# F-rev04.net
KiCad netlist of a schematic drawn in EAGLE
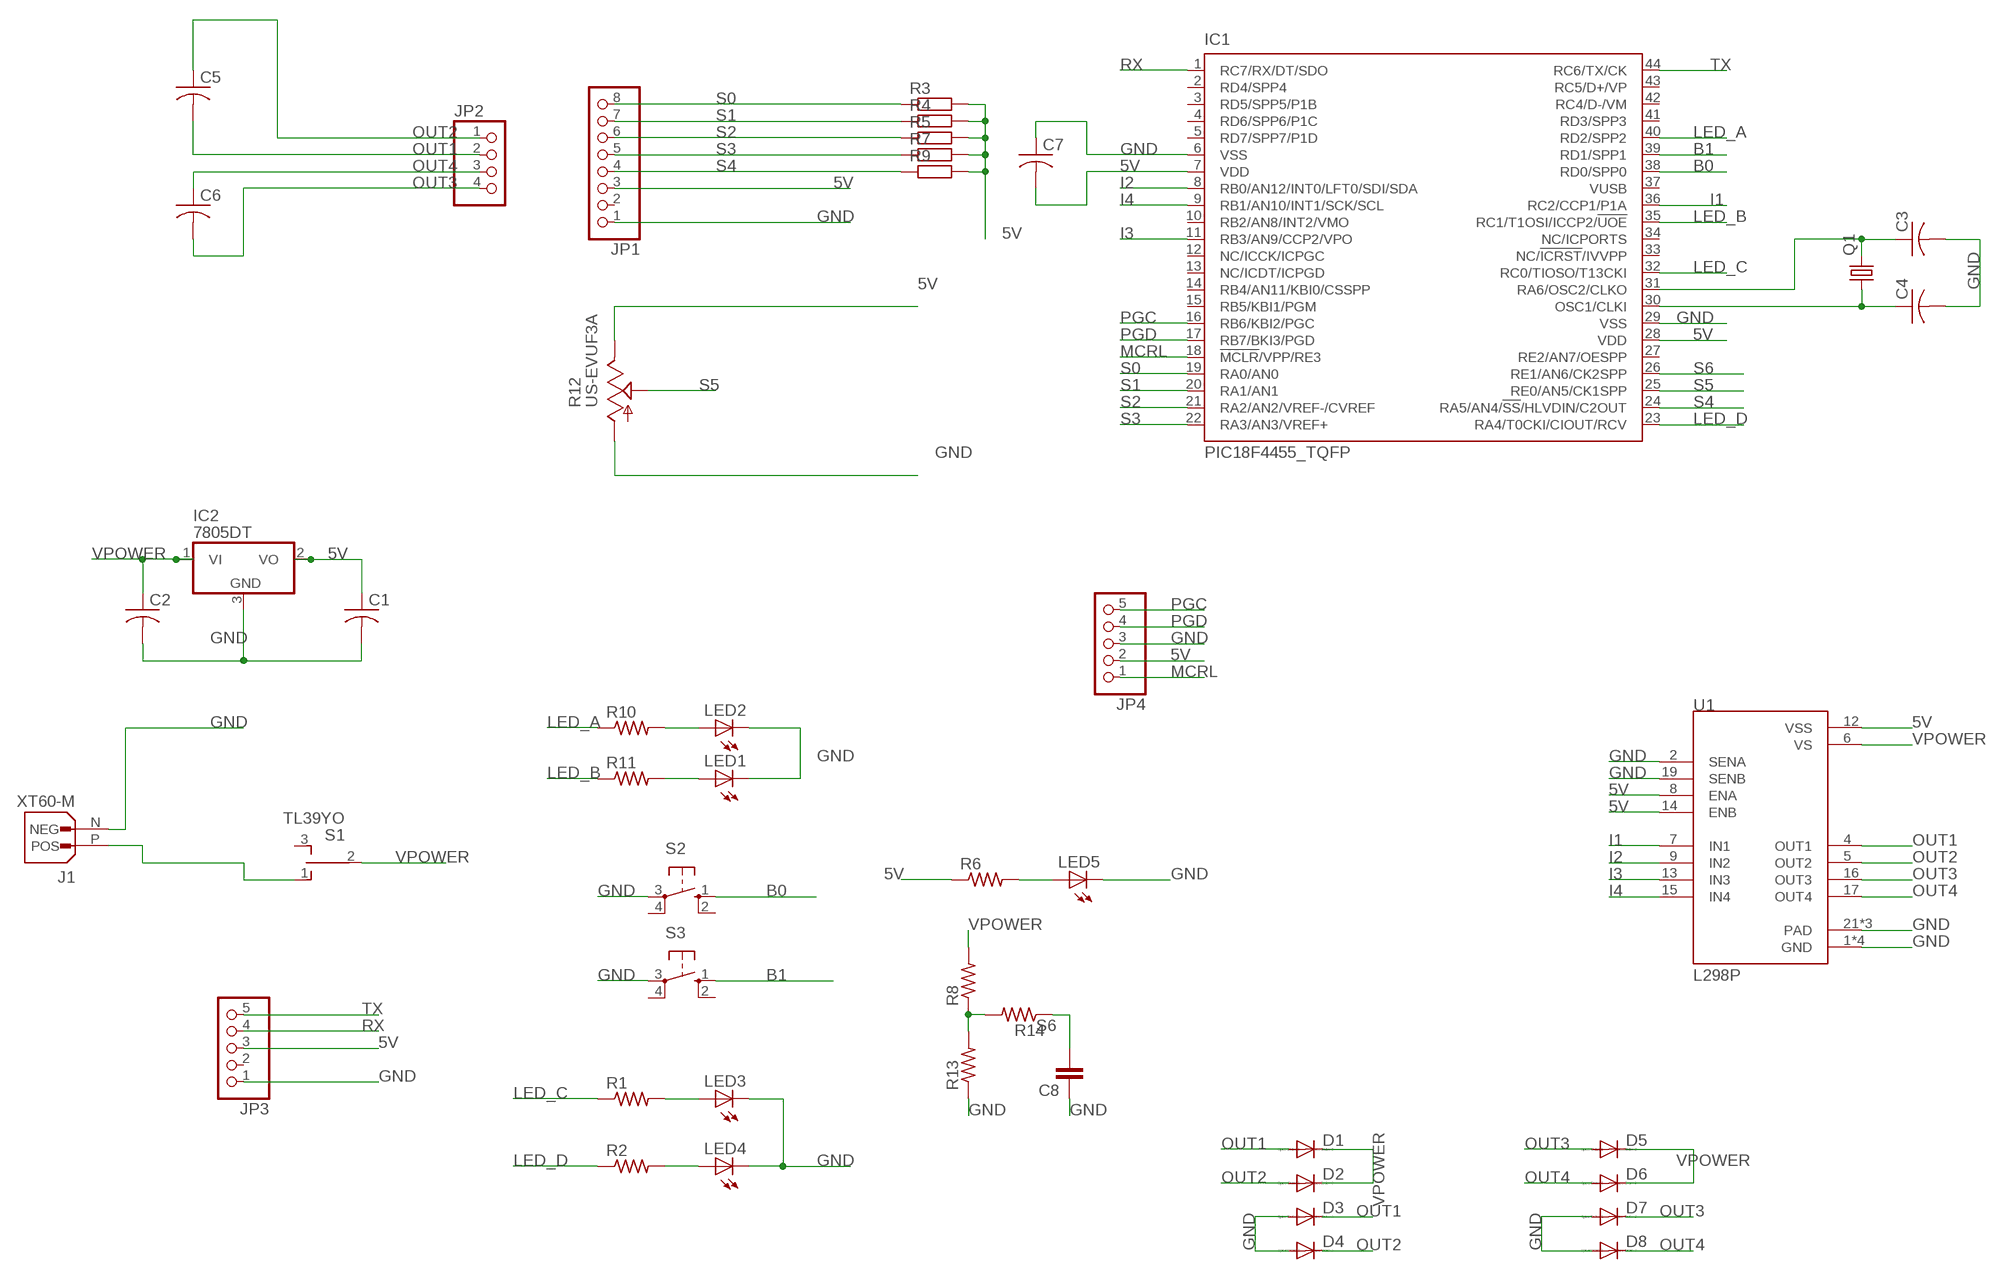
[diagram p0: schematic, sheet 1]

(export (version "E")
  (design (tool "Eeschema 10.0.6"))
  (components
    (comp (ref "C1")
      (value "C-USC0805K")
      (footprint "eagle-import:C0805K")
      (libsource (lib "eagle-import") (part "C-USC0805K"))
    )
    (comp (ref "C2")
      (value "C-USC0805K")
      (footprint "eagle-import:C0805K")
      (libsource (lib "eagle-import") (part "C-USC0805K"))
    )
    (comp (ref "C3")
      (value "C-USC0805K")
      (footprint "eagle-import:C0805K")
      (libsource (lib "eagle-import") (part "C-USC0805K"))
    )
    (comp (ref "C4")
      (value "C-USC0805K")
      (footprint "eagle-import:C0805K")
      (libsource (lib "eagle-import") (part "C-USC0805K"))
    )
    (comp (ref "C5")
      (value "C-USC0805K")
      (footprint "eagle-import:C0805K")
      (libsource (lib "eagle-import") (part "C-USC0805K"))
    )
    (comp (ref "C6")
      (value "C-USC0805K")
      (footprint "eagle-import:C0805K")
      (libsource (lib "eagle-import") (part "C-USC0805K"))
    )
    (comp (ref "C7")
      (value "C-USC0805K")
      (footprint "eagle-import:C0805K")
      (libsource (lib "eagle-import") (part "C-USC0805K"))
    )
    (comp (ref "C8")
      (value "C2,5-3")
      (footprint "eagle-import:C2.5-3")
      (libsource (lib "eagle-import") (part "C2,5-3"))
    )
    (comp (ref "D1")
      (value "DIODE-DO214AC")
      (footprint "eagle-import:DO214AC")
      (libsource (lib "eagle-import") (part "DIODE-DO214AC"))
    )
    (comp (ref "D2")
      (value "DIODE-DO214AC")
      (footprint "eagle-import:DO214AC")
      (libsource (lib "eagle-import") (part "DIODE-DO214AC"))
    )
    (comp (ref "D3")
      (value "DIODE-DO214AC")
      (footprint "eagle-import:DO214AC")
      (libsource (lib "eagle-import") (part "DIODE-DO214AC"))
    )
    (comp (ref "D4")
      (value "DIODE-DO214AC")
      (footprint "eagle-import:DO214AC")
      (libsource (lib "eagle-import") (part "DIODE-DO214AC"))
    )
    (comp (ref "D5")
      (value "DIODE-DO214AC")
      (footprint "eagle-import:DO214AC")
      (libsource (lib "eagle-import") (part "DIODE-DO214AC"))
    )
    (comp (ref "D6")
      (value "DIODE-DO214AC")
      (footprint "eagle-import:DO214AC")
      (libsource (lib "eagle-import") (part "DIODE-DO214AC"))
    )
    (comp (ref "D7")
      (value "DIODE-DO214AC")
      (footprint "eagle-import:DO214AC")
      (libsource (lib "eagle-import") (part "DIODE-DO214AC"))
    )
    (comp (ref "D8")
      (value "DIODE-DO214AC")
      (footprint "eagle-import:DO214AC")
      (libsource (lib "eagle-import") (part "DIODE-DO214AC"))
    )
    (comp (ref "IC1")
      (value "PIC18F4455_TQFP")
      (footprint "eagle-import:TQFP44")
      (fields (field (name "MF") "MICROCHIP") (field (name "MPN") "PIC18F4455-I/PT"))
      (libsource (lib "eagle-import") (part "PIC18F4_TQFP455"))
    )
    (comp (ref "IC2")
      (value "7805DT")
      (footprint "eagle-import:TO252")
      (libsource (lib "eagle-import") (part "78DT05"))
    )
    (comp (ref "J1")
      (value "XT60-M")
      (footprint "eagle-import:AMASS_XT60-M")
      (fields (field (name "MF") "AMASS"))
      (libsource (lib "eagle-import") (part "XT60-M"))
    )
    (comp (ref "JP1")
      (value "PINHD-1X8")
      (footprint "eagle-import:1X08")
      (libsource (lib "eagle-import") (part "PINHD-1X8"))
    )
    (comp (ref "JP2")
      (value "PINHD-1X4")
      (footprint "eagle-import:1X04")
      (libsource (lib "eagle-import") (part "PINHD-1X4"))
    )
    (comp (ref "JP3")
      (value "PINHD-1X5")
      (footprint "eagle-import:1X05")
      (libsource (lib "eagle-import") (part "PINHD-1X5"))
    )
    (comp (ref "JP4")
      (value "PINHD-1X5")
      (footprint "eagle-import:1X05")
      (libsource (lib "eagle-import") (part "PINHD-1X5"))
    )
    (comp (ref "LED1")
      (value "LEDCHIPLED_1206")
      (footprint "eagle-import:CHIPLED_1206")
      (libsource (lib "eagle-import") (part "LEDCHIPLED_1206"))
    )
    (comp (ref "LED2")
      (value "LEDCHIPLED_1206")
      (footprint "eagle-import:CHIPLED_1206")
      (libsource (lib "eagle-import") (part "LEDCHIPLED_1206"))
    )
    (comp (ref "LED3")
      (value "LEDCHIPLED_1206")
      (footprint "eagle-import:CHIPLED_1206")
      (libsource (lib "eagle-import") (part "LEDCHIPLED_1206"))
    )
    (comp (ref "LED4")
      (value "LEDCHIPLED_1206")
      (footprint "eagle-import:CHIPLED_1206")
      (libsource (lib "eagle-import") (part "LEDCHIPLED_1206"))
    )
    (comp (ref "LED5")
      (value "LEDCHIPLED_1206")
      (footprint "eagle-import:CHIPLED_1206")
      (libsource (lib "eagle-import") (part "LEDCHIPLED_1206"))
    )
    (comp (ref "Q1")
      (value "CRYSTALHC49S")
      (footprint "eagle-import:HC49_S")
      (libsource (lib "eagle-import") (part "CRYSTALHC49S"))
    )
    (comp (ref "R1")
      (value "R-US_R0805")
      (footprint "eagle-import:R0805")
      (libsource (lib "eagle-import") (part "resistor_R-US_R0805"))
    )
    (comp (ref "R2")
      (value "R-US_R0805")
      (footprint "eagle-import:R0805")
      (libsource (lib "eagle-import") (part "resistor_R-US_R0805"))
    )
    (comp (ref "R3")
      (value "R-EU_M0805")
      (footprint "eagle-import:M0805")
      (libsource (lib "eagle-import") (part "R-EU_M0805"))
    )
    (comp (ref "R4")
      (value "R-EU_M0805")
      (footprint "eagle-import:M0805")
      (libsource (lib "eagle-import") (part "R-EU_M0805"))
    )
    (comp (ref "R5")
      (value "R-EU_M0805")
      (footprint "eagle-import:M0805")
      (libsource (lib "eagle-import") (part "R-EU_M0805"))
    )
    (comp (ref "R6")
      (value "R-US_M0805")
      (footprint "eagle-import:M0805")
      (libsource (lib "eagle-import") (part "R-US_M0805"))
    )
    (comp (ref "R7")
      (value "R-EU_M0805")
      (footprint "eagle-import:M0805")
      (libsource (lib "eagle-import") (part "R-EU_M0805"))
    )
    (comp (ref "R8")
      (value "R-US_M0805")
      (footprint "eagle-import:M0805")
      (libsource (lib "eagle-import") (part "R-US_M0805"))
    )
    (comp (ref "R9")
      (value "R-EU_M0805")
      (footprint "eagle-import:M0805")
      (libsource (lib "eagle-import") (part "R-EU_M0805"))
    )
    (comp (ref "R10")
      (value "R-US_M0805")
      (footprint "eagle-import:M0805")
      (libsource (lib "eagle-import") (part "R-US_M0805"))
    )
    (comp (ref "R11")
      (value "R-US_M0805")
      (footprint "eagle-import:M0805")
      (libsource (lib "eagle-import") (part "R-US_M0805"))
    )
    (comp (ref "R12")
      (value "US-EVUF3A")
      (footprint "eagle-import:EVUF")
      (libsource (lib "eagle-import") (part "US-EVUAF3"))
    )
    (comp (ref "R13")
      (value "R-US_M0805")
      (footprint "eagle-import:M0805")
      (libsource (lib "eagle-import") (part "R-US_M0805"))
    )
    (comp (ref "R14")
      (value "R-US_M0805")
      (footprint "eagle-import:M0805")
      (libsource (lib "eagle-import") (part "R-US_M0805"))
    )
    (comp (ref "S1")
      (value "TL39YO")
      (footprint "eagle-import:TL3XYO")
      (libsource (lib "eagle-import") (part "TL39YO"))
    )
    (comp (ref "S2")
      (value "10-XX")
      (footprint "eagle-import:B3F-10XX")
      (fields (field (name "MPN") "B3F-1000"))
      (libsource (lib "eagle-import") (part "10-XX"))
    )
    (comp (ref "S3")
      (value "10-XX")
      (footprint "eagle-import:B3F-10XX")
      (fields (field (name "MPN") "B3F-1000"))
      (libsource (lib "eagle-import") (part "10-XX"))
    )
    (comp (ref "U1")
      (value "L298P")
      (footprint "eagle-import:SOIC127P1420X360-20N")
      (fields (field (name "MF") "STMicroelectronics"))
      (libsource (lib "eagle-import") (part "L298P"))
    )
  )
  (nets
    (net (code "1") (name "/5V") (class "Default")
      (node (ref "C1") (pin "1") (pinfunction "1_1") (pintype "passive"))
      (node (ref "C7") (pin "2") (pinfunction "2_2") (pintype "passive"))
      (node (ref "IC1") (pin "28") (pinfunction "VDD_28") (pintype "power_in"))
      (node (ref "IC1") (pin "7") (pinfunction "VDD_7") (pintype "power_in"))
      (node (ref "IC2") (pin "2") (pinfunction "VO_2") (pintype "passive"))
      (node (ref "JP1") (pin "3") (pinfunction "3_3") (pintype "passive"))
      (node (ref "JP3") (pin "3") (pinfunction "3_3") (pintype "passive"))
      (node (ref "JP4") (pin "2") (pinfunction "2_2") (pintype "passive"))
      (node (ref "R12") (pin "3") (pinfunction "E_3") (pintype "passive"))
      (node (ref "R3") (pin "2") (pinfunction "2_2") (pintype "passive"))
      (node (ref "R4") (pin "2") (pinfunction "2_2") (pintype "passive"))
      (node (ref "R5") (pin "2") (pinfunction "2_2") (pintype "passive"))
      (node (ref "R6") (pin "1") (pinfunction "1_1") (pintype "passive"))
      (node (ref "R7") (pin "2") (pinfunction "2_2") (pintype "passive"))
      (node (ref "R9") (pin "2") (pinfunction "2_2") (pintype "passive"))
      (node (ref "U1") (pin "12") (pinfunction "VSS_12") (pintype "power_in"))
      (node (ref "U1") (pin "14") (pinfunction "ENB_14") (pintype "input"))
      (node (ref "U1") (pin "8") (pinfunction "ENA_8") (pintype "input"))
    )
    (net (code "2") (name "/B0") (class "Default")
      (node (ref "IC1") (pin "38") (pinfunction "RD0/SPP0_38") (pintype "bidirectional"))
      (node (ref "S2") (pin "1") (pinfunction "S_1") (pintype "passive"))
    )
    (net (code "3") (name "/B1") (class "Default")
      (node (ref "IC1") (pin "39") (pinfunction "RD1/SPP1_39") (pintype "bidirectional"))
      (node (ref "S3") (pin "1") (pinfunction "S_1") (pintype "passive"))
    )
    (net (code "4") (name "/GND") (class "Default")
      (node (ref "C1") (pin "2") (pinfunction "2_2") (pintype "passive"))
      (node (ref "C2") (pin "2") (pinfunction "2_2") (pintype "passive"))
      (node (ref "C3") (pin "2") (pinfunction "2_2") (pintype "passive"))
      (node (ref "C4") (pin "2") (pinfunction "2_2") (pintype "passive"))
      (node (ref "C7") (pin "1") (pinfunction "1_1") (pintype "passive"))
      (node (ref "C8") (pin "1") (pinfunction "1_1") (pintype "passive"))
      (node (ref "D3") (pin "A") (pinfunction "A_A") (pintype "passive"))
      (node (ref "D4") (pin "A") (pinfunction "A_A") (pintype "passive"))
      (node (ref "D7") (pin "A") (pinfunction "A_A") (pintype "passive"))
      (node (ref "D8") (pin "A") (pinfunction "A_A") (pintype "passive"))
      (node (ref "IC1") (pin "29") (pinfunction "VSS_29") (pintype "power_in"))
      (node (ref "IC1") (pin "6") (pinfunction "VSS_6") (pintype "power_in"))
      (node (ref "IC2") (pin "3") (pinfunction "GND_3") (pintype "passive"))
      (node (ref "J1") (pin "N") (pinfunction "NEG_N") (pintype "passive"))
      (node (ref "JP1") (pin "1") (pinfunction "1_1") (pintype "passive"))
      (node (ref "JP3") (pin "1") (pinfunction "1_1") (pintype "passive"))
      (node (ref "JP4") (pin "3") (pinfunction "3_3") (pintype "passive"))
      (node (ref "LED1") (pin "C") (pinfunction "C_C") (pintype "passive"))
      (node (ref "LED2") (pin "C") (pinfunction "C_C") (pintype "passive"))
      (node (ref "LED3") (pin "C") (pinfunction "C_C") (pintype "passive"))
      (node (ref "LED4") (pin "C") (pinfunction "C_C") (pintype "passive"))
      (node (ref "LED5") (pin "C") (pinfunction "C_C") (pintype "passive"))
      (node (ref "R12") (pin "1") (pinfunction "A_1") (pintype "passive"))
      (node (ref "R13") (pin "1") (pinfunction "1_1") (pintype "passive"))
      (node (ref "S2") (pin "3") (pinfunction "P_3") (pintype "passive"))
      (node (ref "S3") (pin "3") (pinfunction "P_3") (pintype "passive"))
      (node (ref "U1") (pin "1") (pinfunction "GND_1") (pintype "passive"))
      (node (ref "U1") (pin "10") (pinfunction "GND_10") (pintype "passive"))
      (node (ref "U1") (pin "11") (pinfunction "GND_11") (pintype "passive"))
      (node (ref "U1") (pin "19") (pinfunction "SENB_19") (pintype "input"))
      (node (ref "U1") (pin "2") (pinfunction "SENA_2") (pintype "input"))
      (node (ref "U1") (pin "20") (pinfunction "GND_20") (pintype "passive"))
      (node (ref "U1") (pin "21") (pinfunction "PAD_21") (pintype "passive"))
      (node (ref "U1") (pin "22") (pinfunction "PAD_22") (pintype "passive"))
      (node (ref "U1") (pin "23") (pinfunction "PAD_23") (pintype "passive"))
    )
    (net (code "5") (name "/I1") (class "Default")
      (node (ref "IC1") (pin "36") (pinfunction "RC2/CCP1/P1A_36") (pintype "bidirectional"))
      (node (ref "U1") (pin "7") (pinfunction "IN1_7") (pintype "input"))
    )
    (net (code "6") (name "/I2") (class "Default")
      (node (ref "IC1") (pin "8") (pinfunction "RB0/AN12/INT0/LFT0/SDI/SDA_8") (pintype "bidirectional"))
      (node (ref "U1") (pin "9") (pinfunction "IN2_9") (pintype "input"))
    )
    (net (code "7") (name "/I3") (class "Default")
      (node (ref "IC1") (pin "11") (pinfunction "RB3/AN9/CCP2/VPO_11") (pintype "bidirectional"))
      (node (ref "U1") (pin "13") (pinfunction "IN3_13") (pintype "input"))
    )
    (net (code "8") (name "/I4") (class "Default")
      (node (ref "IC1") (pin "9") (pinfunction "RB1/AN10/INT1/SCK/SCL_9") (pintype "bidirectional"))
      (node (ref "U1") (pin "15") (pinfunction "IN4_15") (pintype "input"))
    )
    (net (code "9") (name "/LED_A") (class "Default")
      (node (ref "IC1") (pin "40") (pinfunction "RD2/SPP2_40") (pintype "bidirectional"))
      (node (ref "R10") (pin "1") (pinfunction "1_1") (pintype "passive"))
    )
    (net (code "10") (name "/LED_B") (class "Default")
      (node (ref "IC1") (pin "35") (pinfunction "RC1/T1OSI/ICCP2/~{UOE}_35") (pintype "bidirectional"))
      (node (ref "R11") (pin "1") (pinfunction "1_1") (pintype "passive"))
    )
    (net (code "11") (name "/LED_C") (class "Default")
      (node (ref "IC1") (pin "32") (pinfunction "RC0/TIOSO/T13CKI_32") (pintype "bidirectional"))
      (node (ref "R1") (pin "1") (pinfunction "1_1") (pintype "passive"))
    )
    (net (code "12") (name "/LED_D") (class "Default")
      (node (ref "IC1") (pin "23") (pinfunction "RA4/T0CKI/CIOUT/RCV_23") (pintype "bidirectional"))
      (node (ref "R2") (pin "1") (pinfunction "1_1") (pintype "passive"))
    )
    (net (code "13") (name "/MCRL") (class "Default")
      (node (ref "IC1") (pin "18") (pinfunction "~{MCLR}/VPP/RE3_18") (pintype "input"))
      (node (ref "JP4") (pin "1") (pinfunction "1_1") (pintype "passive"))
    )
    (net (code "14") (name "/OUT1") (class "Default")
      (node (ref "C5") (pin "2") (pinfunction "2_2") (pintype "passive"))
      (node (ref "D1") (pin "A") (pinfunction "A_A") (pintype "passive"))
      (node (ref "D3") (pin "C") (pinfunction "C_C") (pintype "passive"))
      (node (ref "JP2") (pin "2") (pinfunction "2_2") (pintype "passive"))
      (node (ref "U1") (pin "4") (pinfunction "OUT1_4") (pintype "output"))
    )
    (net (code "15") (name "/OUT2") (class "Default")
      (node (ref "C5") (pin "1") (pinfunction "1_1") (pintype "passive"))
      (node (ref "D2") (pin "A") (pinfunction "A_A") (pintype "passive"))
      (node (ref "D4") (pin "C") (pinfunction "C_C") (pintype "passive"))
      (node (ref "JP2") (pin "1") (pinfunction "1_1") (pintype "passive"))
      (node (ref "U1") (pin "5") (pinfunction "OUT2_5") (pintype "output"))
    )
    (net (code "16") (name "/OUT3") (class "Default")
      (node (ref "C6") (pin "2") (pinfunction "2_2") (pintype "passive"))
      (node (ref "D5") (pin "A") (pinfunction "A_A") (pintype "passive"))
      (node (ref "D7") (pin "C") (pinfunction "C_C") (pintype "passive"))
      (node (ref "JP2") (pin "4") (pinfunction "4_4") (pintype "passive"))
      (node (ref "U1") (pin "16") (pinfunction "OUT3_16") (pintype "output"))
    )
    (net (code "17") (name "/OUT4") (class "Default")
      (node (ref "C6") (pin "1") (pinfunction "1_1") (pintype "passive"))
      (node (ref "D6") (pin "A") (pinfunction "A_A") (pintype "passive"))
      (node (ref "D8") (pin "C") (pinfunction "C_C") (pintype "passive"))
      (node (ref "JP2") (pin "3") (pinfunction "3_3") (pintype "passive"))
      (node (ref "U1") (pin "17") (pinfunction "OUT4_17") (pintype "output"))
    )
    (net (code "18") (name "/PGC") (class "Default")
      (node (ref "IC1") (pin "16") (pinfunction "RB6/KBI2/PGC_16") (pintype "bidirectional"))
      (node (ref "JP4") (pin "5") (pinfunction "5_5") (pintype "passive"))
    )
    (net (code "19") (name "/PGD") (class "Default")
      (node (ref "IC1") (pin "17") (pinfunction "RB7/BKI3/PGD_17") (pintype "bidirectional"))
      (node (ref "JP4") (pin "4") (pinfunction "4_4") (pintype "passive"))
    )
    (net (code "20") (name "/RX") (class "Default")
      (node (ref "IC1") (pin "1") (pinfunction "RC7/RX/DT/SDO_1") (pintype "bidirectional"))
      (node (ref "JP3") (pin "4") (pinfunction "4_4") (pintype "passive"))
    )
    (net (code "21") (name "/S0") (class "Default")
      (node (ref "IC1") (pin "19") (pinfunction "RA0/AN0_19") (pintype "bidirectional"))
      (node (ref "JP1") (pin "8") (pinfunction "8_8") (pintype "passive"))
      (node (ref "R3") (pin "1") (pinfunction "1_1") (pintype "passive"))
    )
    (net (code "22") (name "/S1") (class "Default")
      (node (ref "IC1") (pin "20") (pinfunction "RA1/AN1_20") (pintype "bidirectional"))
      (node (ref "JP1") (pin "7") (pinfunction "7_7") (pintype "passive"))
      (node (ref "R4") (pin "1") (pinfunction "1_1") (pintype "passive"))
    )
    (net (code "23") (name "/S2") (class "Default")
      (node (ref "IC1") (pin "21") (pinfunction "RA2/AN2/VREF-/CVREF_21") (pintype "bidirectional"))
      (node (ref "JP1") (pin "6") (pinfunction "6_6") (pintype "passive"))
      (node (ref "R5") (pin "1") (pinfunction "1_1") (pintype "passive"))
    )
    (net (code "24") (name "/S3") (class "Default")
      (node (ref "IC1") (pin "22") (pinfunction "RA3/AN3/VREF+_22") (pintype "bidirectional"))
      (node (ref "JP1") (pin "5") (pinfunction "5_5") (pintype "passive"))
      (node (ref "R7") (pin "1") (pinfunction "1_1") (pintype "passive"))
    )
    (net (code "25") (name "/S4") (class "Default")
      (node (ref "IC1") (pin "24") (pinfunction "RA5/AN4/~{SS}/HLVDIN/C2OUT_24") (pintype "bidirectional"))
      (node (ref "JP1") (pin "4") (pinfunction "4_4") (pintype "passive"))
      (node (ref "R9") (pin "1") (pinfunction "1_1") (pintype "passive"))
    )
    (net (code "26") (name "/S5") (class "Default")
      (node (ref "IC1") (pin "25") (pinfunction "RE0/AN5/CK1SPP_25") (pintype "bidirectional"))
      (node (ref "R12") (pin "2") (pinfunction "S_2") (pintype "passive"))
    )
    (net (code "27") (name "/S6") (class "Default")
      (node (ref "C8") (pin "2") (pinfunction "2_2") (pintype "passive"))
      (node (ref "IC1") (pin "26") (pinfunction "RE1/AN6/CK2SPP_26") (pintype "bidirectional"))
      (node (ref "R14") (pin "1") (pinfunction "1_1") (pintype "passive"))
    )
    (net (code "28") (name "/TX") (class "Default")
      (node (ref "IC1") (pin "44") (pinfunction "RC6/TX/CK_44") (pintype "bidirectional"))
      (node (ref "JP3") (pin "5") (pinfunction "5_5") (pintype "passive"))
    )
    (net (code "29") (name "/VPOWER") (class "Default")
      (node (ref "C2") (pin "1") (pinfunction "1_1") (pintype "passive"))
      (node (ref "D1") (pin "C") (pinfunction "C_C") (pintype "passive"))
      (node (ref "D2") (pin "C") (pinfunction "C_C") (pintype "passive"))
      (node (ref "D5") (pin "C") (pinfunction "C_C") (pintype "passive"))
      (node (ref "D6") (pin "C") (pinfunction "C_C") (pintype "passive"))
      (node (ref "IC2") (pin "1") (pinfunction "VI_1") (pintype "input"))
      (node (ref "R8") (pin "2") (pinfunction "2_2") (pintype "passive"))
      (node (ref "S1") (pin "2") (pinfunction "P_2") (pintype "passive"))
      (node (ref "U1") (pin "6") (pinfunction "VS_6") (pintype "power_in"))
    )
    (net (code "30") (name "Net-(IC1-OSC1{slash}CLKI)") (class "Default")
      (node (ref "C4") (pin "1") (pinfunction "1_1") (pintype "passive"))
      (node (ref "IC1") (pin "30") (pinfunction "OSC1/CLKI_30") (pintype "input"))
      (node (ref "Q1") (pin "1") (pinfunction "1_1") (pintype "passive"))
    )
    (net (code "31") (name "Net-(IC1-RA6{slash}OSC2{slash}CLKO)") (class "Default")
      (node (ref "C3") (pin "1") (pinfunction "1_1") (pintype "passive"))
      (node (ref "IC1") (pin "31") (pinfunction "RA6/OSC2/CLKO_31") (pintype "output"))
      (node (ref "Q1") (pin "2") (pinfunction "2_2") (pintype "passive"))
    )
    (net (code "32") (name "Net-(J1-POS)") (class "Default")
      (node (ref "J1") (pin "P") (pinfunction "POS_P") (pintype "passive"))
      (node (ref "S1") (pin "1") (pinfunction "O_1") (pintype "passive"))
    )
    (net (code "33") (name "Net-(LED1-PadA)") (class "Default")
      (node (ref "LED1") (pin "A") (pinfunction "A_A") (pintype "passive"))
      (node (ref "R11") (pin "2") (pinfunction "2_2") (pintype "passive"))
    )
    (net (code "34") (name "Net-(LED2-PadA)") (class "Default")
      (node (ref "LED2") (pin "A") (pinfunction "A_A") (pintype "passive"))
      (node (ref "R10") (pin "2") (pinfunction "2_2") (pintype "passive"))
    )
    (net (code "35") (name "Net-(LED3-PadA)") (class "Default")
      (node (ref "LED3") (pin "A") (pinfunction "A_A") (pintype "passive"))
      (node (ref "R1") (pin "2") (pinfunction "2_2") (pintype "passive"))
    )
    (net (code "36") (name "Net-(LED4-PadA)") (class "Default")
      (node (ref "LED4") (pin "A") (pinfunction "A_A") (pintype "passive"))
      (node (ref "R2") (pin "2") (pinfunction "2_2") (pintype "passive"))
    )
    (net (code "37") (name "Net-(LED5-PadA)") (class "Default")
      (node (ref "LED5") (pin "A") (pinfunction "A_A") (pintype "passive"))
      (node (ref "R6") (pin "2") (pinfunction "2_2") (pintype "passive"))
    )
    (net (code "38") (name "Net-(R13-Pad2)") (class "Default")
      (node (ref "R13") (pin "2") (pinfunction "2_2") (pintype "passive"))
      (node (ref "R14") (pin "2") (pinfunction "2_2") (pintype "passive"))
      (node (ref "R8") (pin "1") (pinfunction "1_1") (pintype "passive"))
    )
    (net (code "39") (name "unconnected-(IC1-NC{slash}ICCK{slash}ICPGC-Pad12)") (class "Default")
      (node (ref "IC1") (pin "12") (pinfunction "NC/ICCK/ICPGC_12") (pintype "bidirectional"))
    )
    (net (code "40") (name "unconnected-(IC1-NC{slash}ICDT{slash}ICPGD-Pad13)") (class "Default")
      (node (ref "IC1") (pin "13") (pinfunction "NC/ICDT/ICPGD_13") (pintype "bidirectional"))
    )
    (net (code "41") (name "unconnected-(IC1-NC{slash}ICPORTS-Pad34)") (class "Default")
      (node (ref "IC1") (pin "34") (pinfunction "NC/ICPORTS_34") (pintype "input"))
    )
    (net (code "42") (name "unconnected-(IC1-NC{slash}~{ICRST}{slash}IVVPP-Pad33)") (class "Default")
      (node (ref "IC1") (pin "33") (pinfunction "NC/~{ICRST}/IVVPP_33") (pintype "input"))
    )
    (net (code "43") (name "unconnected-(IC1-RB2{slash}AN8{slash}INT2{slash}VMO-Pad10)") (class "Default")
      (node (ref "IC1") (pin "10") (pinfunction "RB2/AN8/INT2/VMO_10") (pintype "bidirectional"))
    )
    (net (code "44") (name "unconnected-(IC1-RB4{slash}AN11{slash}KBI0{slash}CSSPP-Pad14)") (class "Default")
      (node (ref "IC1") (pin "14") (pinfunction "RB4/AN11/KBI0/CSSPP_14") (pintype "bidirectional"))
    )
    (net (code "45") (name "unconnected-(IC1-RB5{slash}KBI1{slash}PGM-Pad15)") (class "Default")
      (node (ref "IC1") (pin "15") (pinfunction "RB5/KBI1/PGM_15") (pintype "bidirectional"))
    )
    (net (code "46") (name "unconnected-(IC1-RC4{slash}D-{slash}VM-Pad42)") (class "Default")
      (node (ref "IC1") (pin "42") (pinfunction "RC4/D-/VM_42") (pintype "bidirectional"))
    )
    (net (code "47") (name "unconnected-(IC1-RC5{slash}D+{slash}VP-Pad43)") (class "Default")
      (node (ref "IC1") (pin "43") (pinfunction "RC5/D+/VP_43") (pintype "bidirectional"))
    )
    (net (code "48") (name "unconnected-(IC1-RD3{slash}SPP3-Pad41)") (class "Default")
      (node (ref "IC1") (pin "41") (pinfunction "RD3/SPP3_41") (pintype "bidirectional"))
    )
    (net (code "49") (name "unconnected-(IC1-RD4{slash}SPP4-Pad2)") (class "Default")
      (node (ref "IC1") (pin "2") (pinfunction "RD4/SPP4_2") (pintype "bidirectional"))
    )
    (net (code "50") (name "unconnected-(IC1-RD5{slash}SPP5{slash}P1B-Pad3)") (class "Default")
      (node (ref "IC1") (pin "3") (pinfunction "RD5/SPP5/P1B_3") (pintype "bidirectional"))
    )
    (net (code "51") (name "unconnected-(IC1-RD6{slash}SPP6{slash}P1C-Pad4)") (class "Default")
      (node (ref "IC1") (pin "4") (pinfunction "RD6/SPP6/P1C_4") (pintype "bidirectional"))
    )
    (net (code "52") (name "unconnected-(IC1-RD7{slash}SPP7{slash}P1D-Pad5)") (class "Default")
      (node (ref "IC1") (pin "5") (pinfunction "RD7/SPP7/P1D_5") (pintype "bidirectional"))
    )
    (net (code "53") (name "unconnected-(IC1-RE2{slash}AN7{slash}OESPP-Pad27)") (class "Default")
      (node (ref "IC1") (pin "27") (pinfunction "RE2/AN7/OESPP_27") (pintype "bidirectional"))
    )
    (net (code "54") (name "unconnected-(IC1-VUSB-Pad37)") (class "Default")
      (node (ref "IC1") (pin "37") (pinfunction "VUSB_37") (pintype "bidirectional"))
    )
    (net (code "55") (name "unconnected-(JP1-Pad2)") (class "Default")
      (node (ref "JP1") (pin "2") (pinfunction "2_2") (pintype "passive"))
    )
    (net (code "56") (name "unconnected-(JP3-Pad2)") (class "Default")
      (node (ref "JP3") (pin "2") (pinfunction "2_2") (pintype "passive"))
    )
    (net (code "57") (name "unconnected-(S1-S-Pad3)") (class "Default")
      (node (ref "S1") (pin "3") (pinfunction "S_3") (pintype "passive"))
    )
    (net (code "58") (name "unconnected-(S2-P1-Pad4)") (class "Default")
      (node (ref "S2") (pin "4") (pinfunction "P1_4") (pintype "passive"))
    )
    (net (code "59") (name "unconnected-(S2-S1-Pad2)") (class "Default")
      (node (ref "S2") (pin "2") (pinfunction "S1_2") (pintype "passive"))
    )
    (net (code "60") (name "unconnected-(S3-P1-Pad4)") (class "Default")
      (node (ref "S3") (pin "4") (pinfunction "P1_4") (pintype "passive"))
    )
    (net (code "61") (name "unconnected-(S3-S1-Pad2)") (class "Default")
      (node (ref "S3") (pin "2") (pinfunction "S1_2") (pintype "passive"))
    )
  )
)
